# supply.net
KiCad netlist of a schematic drawn in Altium Designer
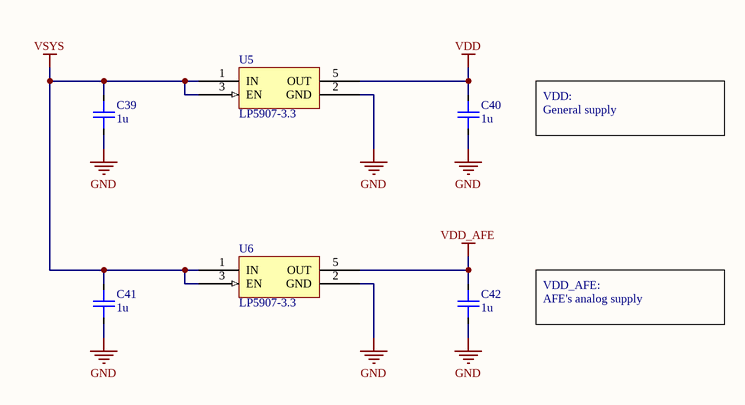
[diagram p0: supply.SchDoc]

(export (version "E")
  (design (tool "Eeschema 10.0.6"))
  (components
    (comp (ref "C39")
      (value "1u")
      (footprint "C0402")
      (description "Capacitor")
      (libsource (lib "misc") (part "Capacitor"))
    )
    (comp (ref "C40")
      (value "1u")
      (footprint "C0402")
      (description "Capacitor")
      (libsource (lib "misc") (part "Capacitor"))
    )
    (comp (ref "C41")
      (value "1u")
      (footprint "C0402")
      (description "Capacitor")
      (libsource (lib "misc") (part "Capacitor"))
    )
    (comp (ref "C42")
      (value "1u")
      (footprint "C0402")
      (description "Capacitor")
      (libsource (lib "misc") (part "Capacitor"))
    )
    (comp (ref "U5")
      (value "LP5907-3.3")
      (footprint "LP5907")
      (description "IC - Voltage Regulator, Linear")
      (libsource (lib "ecg-go") (part "LP5907-3.3"))
    )
    (comp (ref "U6")
      (value "LP5907-3.3")
      (footprint "LP5907")
      (description "IC - Voltage Regulator, Linear")
      (libsource (lib "ecg-go") (part "LP5907-3.3"))
    )
  )
  (nets
    (net (code "1") (name "GND") (class "Default")
      (node (ref "C39") (pin "1") (pinfunction "1_1") (pintype "passive"))
      (node (ref "C40") (pin "1") (pinfunction "1_1") (pintype "passive"))
      (node (ref "C41") (pin "1") (pinfunction "1_1") (pintype "passive"))
      (node (ref "C42") (pin "1") (pinfunction "1_1") (pintype "passive"))
      (node (ref "U5") (pin "2") (pinfunction "GND_2") (pintype "power_in"))
      (node (ref "U6") (pin "2") (pinfunction "GND_2") (pintype "power_in"))
    )
    (net (code "2") (name "VDD") (class "Default")
      (node (ref "C40") (pin "2") (pinfunction "2_2") (pintype "passive"))
      (node (ref "U5") (pin "5") (pinfunction "OUT_5") (pintype "power_in"))
    )
    (net (code "3") (name "VDD_AFE") (class "Default")
      (node (ref "C42") (pin "2") (pinfunction "2_2") (pintype "passive"))
      (node (ref "U6") (pin "5") (pinfunction "OUT_5") (pintype "power_in"))
    )
    (net (code "4") (name "VSYS") (class "Default")
      (node (ref "C39") (pin "2") (pinfunction "2_2") (pintype "passive"))
      (node (ref "C41") (pin "2") (pinfunction "2_2") (pintype "passive"))
      (node (ref "U5") (pin "1") (pinfunction "IN_1") (pintype "power_in"))
      (node (ref "U5") (pin "3") (pinfunction "EN_3") (pintype "input"))
      (node (ref "U6") (pin "1") (pinfunction "IN_1") (pintype "power_in"))
      (node (ref "U6") (pin "3") (pinfunction "EN_3") (pintype "input"))
    )
  )
)
